# ProProject_Access_Control_KMX_Switch_202.net
KiCad netlist of a schematic drawn in EasyEDA Pro
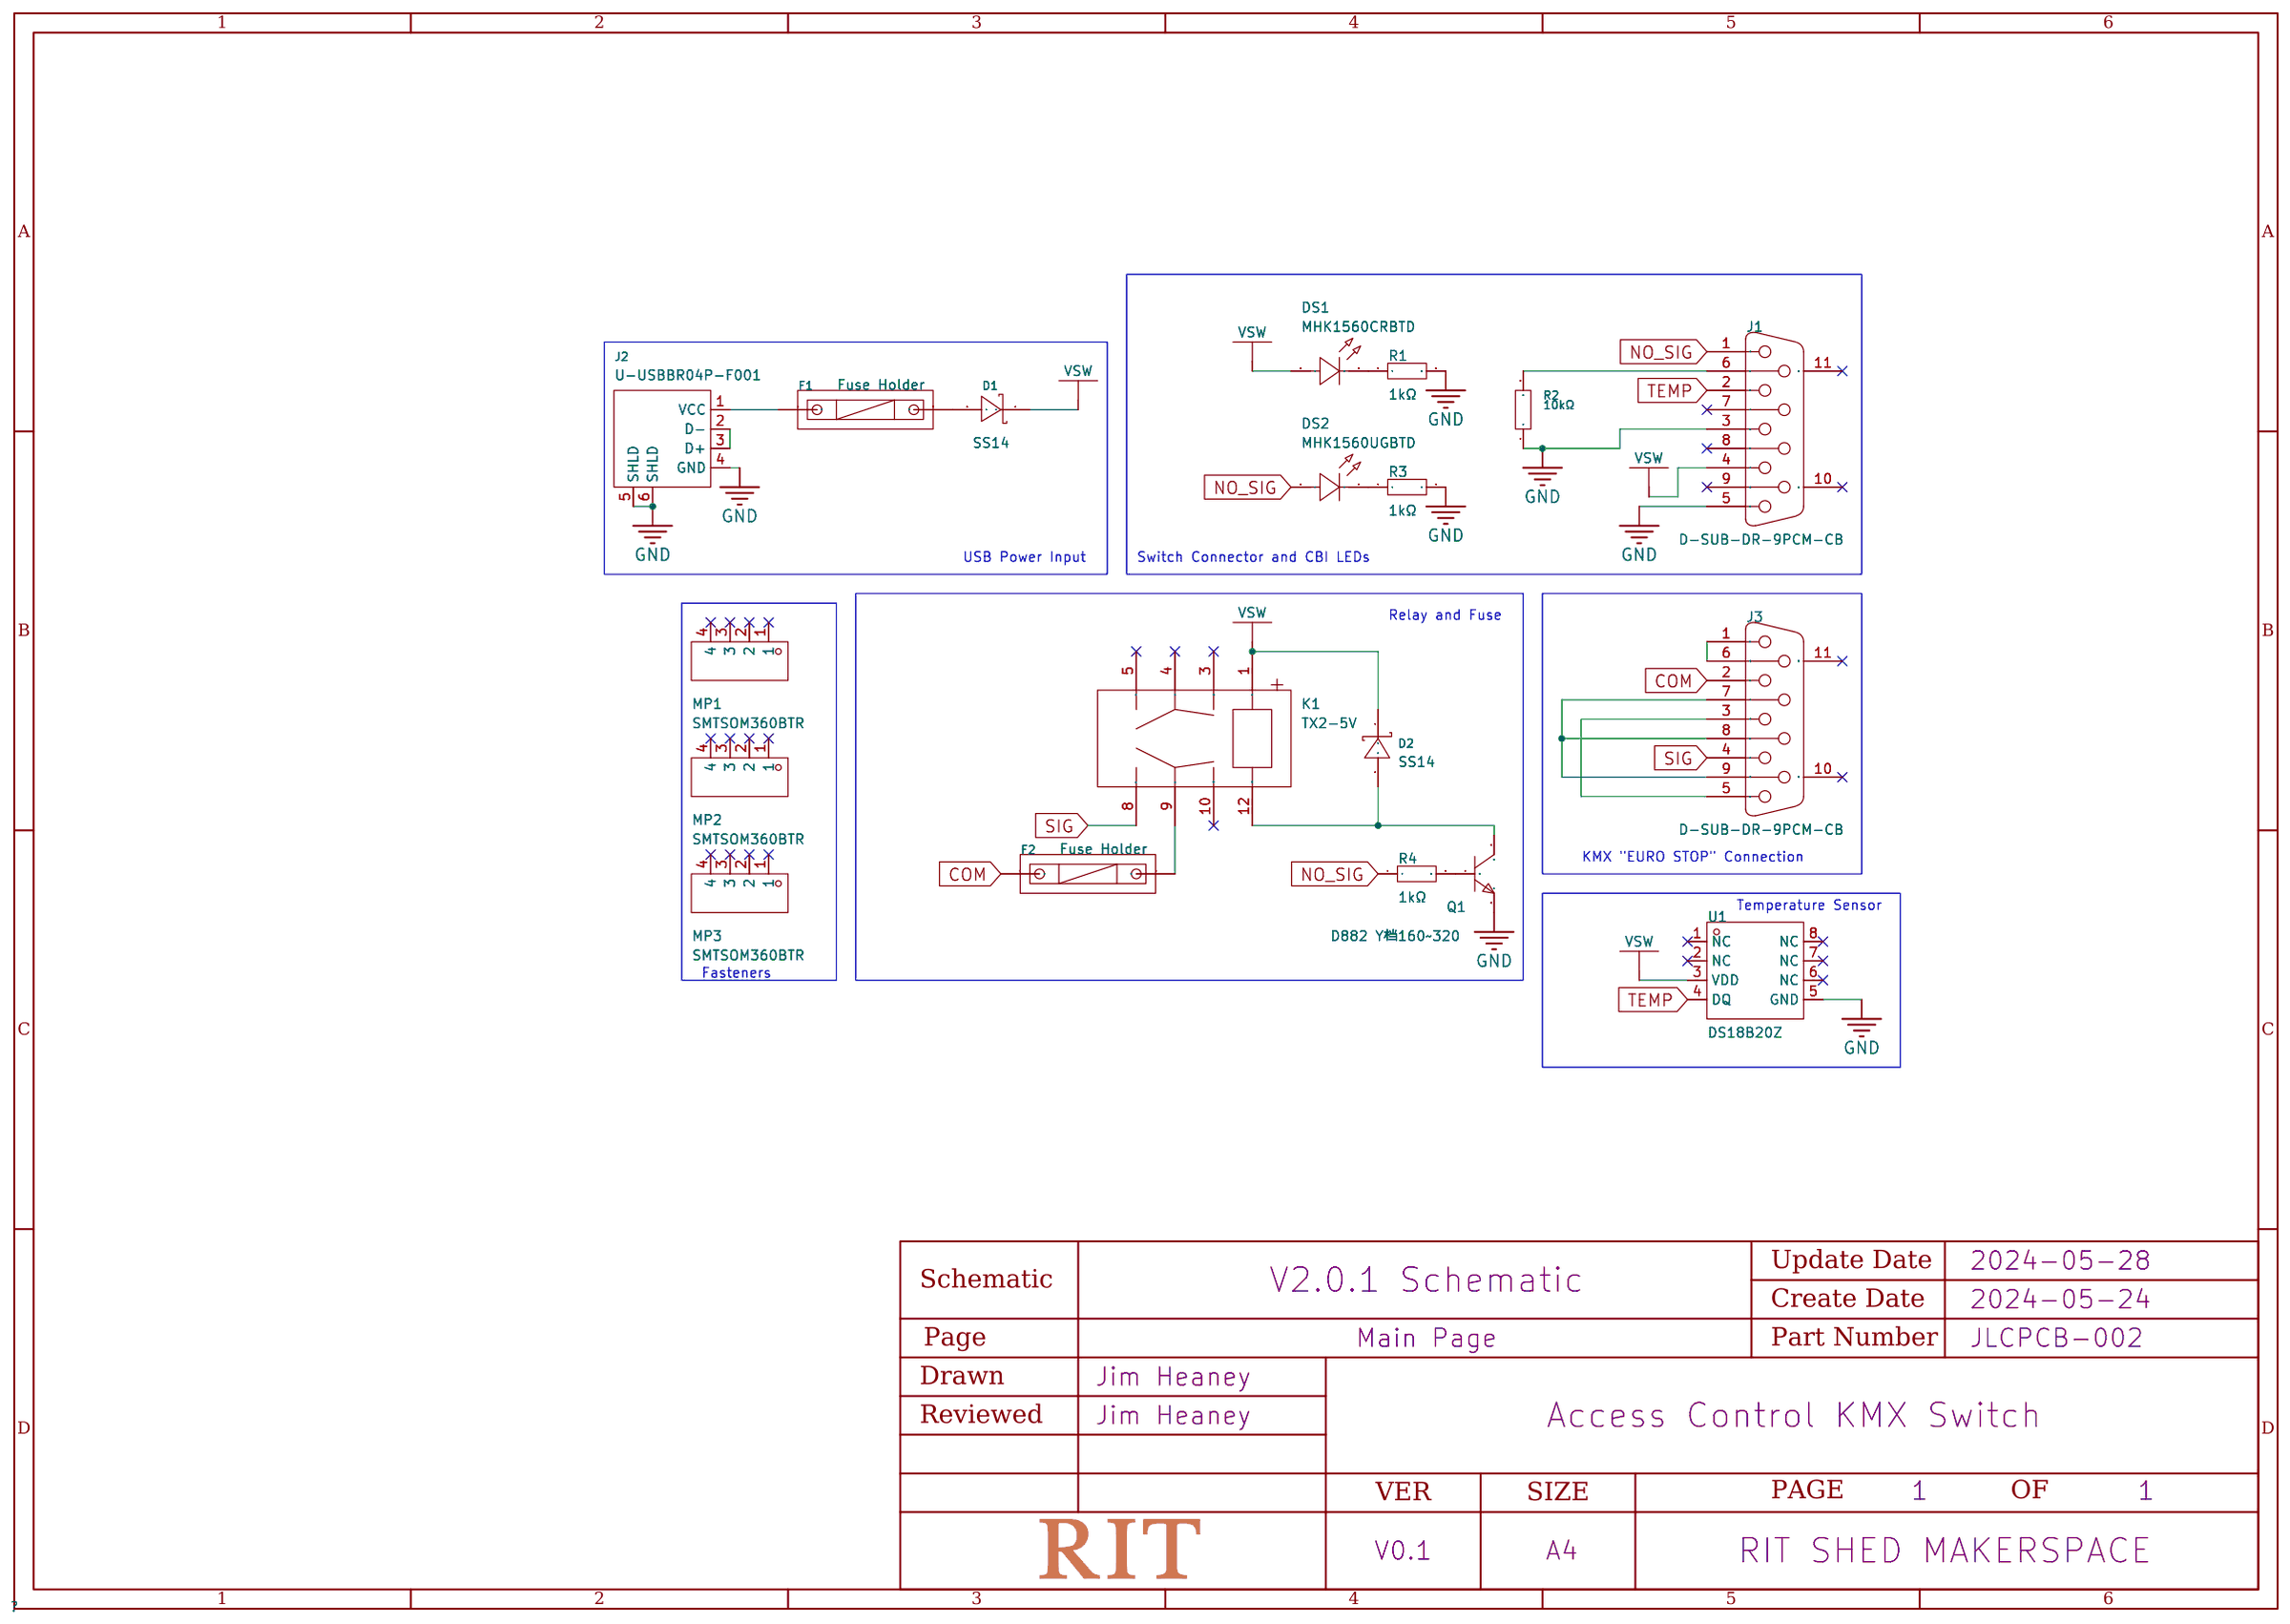
[diagram p0: schematic sheet]

(export (version "E")
  (design (tool "Eeschema 10.0.6"))
  (components
    (comp (ref "D1")
      (value "SS14")
      (footprint "easyedapro:SMA_L4.2-W2.6-LS5.3-RD")
      (fields (field (name "Manufacturer") "MDD"))
      (libsource (lib "easyedapro") (part "SS14"))
    )
    (comp (ref "D2")
      (value "SS14")
      (footprint "easyedapro:SMA_L4.2-W2.6-LS5.3-RD")
      (fields (field (name "Manufacturer") "MDD"))
      (libsource (lib "easyedapro") (part "SS14"))
    )
    (comp (ref "DS1")
      (value "MHK1560CRBTD")
      (footprint "easyedapro:LED-TH_MHK1560UGBTD")
      (fields (field (name "Manufacturer") "MEIHUA(美华)"))
      (libsource (lib "easyedapro") (part "MHK1560CGBTD"))
    )
    (comp (ref "DS2")
      (value "MHK1560UGBTD")
      (footprint "easyedapro:LED-TH_MHK1560UGBTD")
      (fields (field (name "Manufacturer") "MEIHUA(美华)"))
      (libsource (lib "easyedapro") (part "MHK1560UGBTD"))
    )
    (comp (ref "F1")
      (value "Fuse Holder")
      (footprint "easyedapro:FUSE-TH_L24.5-W9.8-P22.5")
      (description "Fuseholder Type:- Fuse Type:- Fuse Size:-")
      (fields (field (name "Manufacturer Part") "保险丝透明座") (field (name "Manufacturer") "xcfuse(旭程)"))
      (libsource (lib "easyedapro") (part "Fuse transparent seat"))
    )
    (comp (ref "F2")
      (value "Fuse Holder")
      (footprint "easyedapro:FUSE-TH_L24.5-W9.8-P22.5")
      (description "Fuseholder Type:- Fuse Type:- Fuse Size:-")
      (fields (field (name "Manufacturer Part") "保险丝透明座") (field (name "Manufacturer") "xcfuse(旭程)"))
      (libsource (lib "easyedapro") (part "Fuse transparent seat"))
    )
    (comp (ref "J1")
      (value "D-SUB-DR-9PCM-CB")
      (footprint "easyedapro:DB9-TH_ID09S33E4GV00LF")
      (fields (field (name "Manufacturer") "XUNPU(讯普)"))
      (libsource (lib "easyedapro") (part "D-SUB-DR-9PCM-CB"))
    )
    (comp (ref "J2")
      (value "U-USBBR04P-F001")
      (footprint "easyedapro:USB-B-TH_U241-041N-1BR85-1")
      (fields (field (name "Manufacturer") "Ckmtw(灿科盟)"))
      (libsource (lib "easyedapro") (part "U-USBBR04P-F001"))
    )
    (comp (ref "J3")
      (value "D-SUB-DR-9PCM-CB")
      (footprint "easyedapro:DB9-TH_ID09S33E4GV00LF")
      (fields (field (name "Manufacturer") "XUNPU(讯普)"))
      (libsource (lib "easyedapro") (part "D-SUB-DR-9PCM-CB"))
    )
    (comp (ref "K1")
      (value "TX2-5V")
      (footprint "easyedapro:RELAY-TH_TX2-3V")
      (fields (field (name "Manufacturer") "PANASONIC(松下)"))
      (libsource (lib "easyedapro") (part "TX2-5V"))
    )
    (comp (ref "MP1")
      (value "SMTSOM360BTR")
      (footprint "easyedapro:SMD_BD5.6-D4.1")
      (fields (field (name "Manufacturer") "YIYUAN(怡远)"))
      (libsource (lib "easyedapro") (part "SMTSOM360BTR"))
    )
    (comp (ref "MP2")
      (value "SMTSOM360BTR")
      (footprint "easyedapro:SMD_BD5.6-D4.1")
      (fields (field (name "Manufacturer") "YIYUAN(怡远)"))
      (libsource (lib "easyedapro") (part "SMTSOM360BTR"))
    )
    (comp (ref "MP3")
      (value "SMTSOM360BTR")
      (footprint "easyedapro:SMD_BD5.6-D4.1")
      (fields (field (name "Manufacturer") "YIYUAN(怡远)"))
      (libsource (lib "easyedapro") (part "SMTSOM360BTR"))
    )
    (comp (ref "Q1")
      (value "D882 Y档160~320")
      (footprint "easyedapro:SOT-89-3_L4.5-W2.5-P1.50-LS4.2-BR")
      (fields (field (name "Manufacturer") "CJ(江苏长电/长晶)"))
      (libsource (lib "easyedapro") (part "D882_C9634"))
    )
    (comp (ref "R1")
      (value "1kΩ")
      (footprint "easyedapro:R0805")
      (fields
        (field (name "Manufacturer Part") "0805W8F1001T5E")
        (field (name "Manufacturer") "UNI-ROYAL(厚声)")
      )
      (libsource (lib "easyedapro") (part "0805W8F1001T5E"))
    )
    (comp (ref "R2")
      (value "10kΩ")
      (footprint "easyedapro:R0805")
      (fields
        (field (name "Manufacturer Part") "0805W8F1002T5E")
        (field (name "Manufacturer") "UNI-ROYAL(厚声)")
      )
      (libsource (lib "easyedapro") (part "0805W8F1002T5E"))
    )
    (comp (ref "R3")
      (value "1kΩ")
      (footprint "easyedapro:R0805")
      (fields
        (field (name "Manufacturer Part") "0805W8F1001T5E")
        (field (name "Manufacturer") "UNI-ROYAL(厚声)")
      )
      (libsource (lib "easyedapro") (part "0805W8F1001T5E"))
    )
    (comp (ref "R4")
      (value "1kΩ")
      (footprint "easyedapro:R0805")
      (fields
        (field (name "Manufacturer Part") "0805W8F1001T5E")
        (field (name "Manufacturer") "UNI-ROYAL(厚声)")
      )
      (libsource (lib "easyedapro") (part "0805W8F1001T5E"))
    )
    (comp (ref "U1")
      (value "DS18B20Z")
      (footprint "easyedapro:SOP-8_L4.9-W3.9-P1.27-LS6.0-BL")
      (description "Resolution:±0.4°C Resolution:±0.4°C Supply Voltage:2.5V~5.5V Supply Voltage:2.5V~5.5V")
      (fields (field (name "Manufacturer") "UMW(友台半导体)"))
      (libsource (lib "easyedapro") (part "DS18B20Z"))
    )
  )
  (nets
    (net (code "1") (name "COM") (class "Default")
      (node (ref "F2") (pin "1") (pinfunction "1_1") (pintype "input"))
      (node (ref "J3") (pin "2") (pinfunction "2_2") (pintype "input"))
    )
    (net (code "2") (name "GND") (class "Default")
      (node (ref "J1") (pin "3") (pinfunction "3_3") (pintype "input"))
      (node (ref "J1") (pin "5") (pinfunction "5_5") (pintype "input"))
      (node (ref "J2") (pin "4") (pinfunction "GND_4") (pintype "input"))
      (node (ref "J2") (pin "5") (pinfunction "SHLD_5") (pintype "input"))
      (node (ref "J2") (pin "6") (pinfunction "SHLD_6") (pintype "input"))
      (node (ref "Q1") (pin "3") (pinfunction "E_3") (pintype "input"))
      (node (ref "R1") (pin "2") (pinfunction "2_2") (pintype "input"))
      (node (ref "R2") (pin "1") (pinfunction "1_1") (pintype "input"))
      (node (ref "R3") (pin "2") (pinfunction "2_2") (pintype "input"))
      (node (ref "U1") (pin "5") (pinfunction "GND_5") (pintype "unspecified"))
    )
    (net (code "3") (name "NO_SIG") (class "Default")
      (node (ref "DS2") (pin "2") (pinfunction "A_2") (pintype "unspecified"))
      (node (ref "J1") (pin "1") (pinfunction "1_1") (pintype "input"))
      (node (ref "R4") (pin "1") (pinfunction "1_1") (pintype "input"))
    )
    (net (code "4") (name "Net-(D1-A)") (class "Default")
      (node (ref "D1") (pin "2") (pinfunction "A_2") (pintype "input"))
      (node (ref "F1") (pin "2") (pinfunction "2_2") (pintype "input"))
    )
    (net (code "5") (name "Net-(D2-A)") (class "Default")
      (node (ref "D2") (pin "2") (pinfunction "A_2") (pintype "input"))
      (node (ref "K1") (pin "12") (pinfunction "12_12") (pintype "input"))
      (node (ref "Q1") (pin "2") (pinfunction "C_2") (pintype "input"))
    )
    (net (code "6") (name "Net-(DS1-K)") (class "Default")
      (node (ref "DS1") (pin "1") (pinfunction "K_1") (pintype "unspecified"))
      (node (ref "R1") (pin "1") (pinfunction "1_1") (pintype "input"))
    )
    (net (code "7") (name "Net-(DS2-K)") (class "Default")
      (node (ref "DS2") (pin "1") (pinfunction "K_1") (pintype "unspecified"))
      (node (ref "R3") (pin "1") (pinfunction "1_1") (pintype "input"))
    )
    (net (code "8") (name "Net-(F2-Pad2)") (class "Default")
      (node (ref "F2") (pin "2") (pinfunction "2_2") (pintype "input"))
      (node (ref "K1") (pin "9") (pinfunction "9_9") (pintype "input"))
    )
    (net (code "9") (name "Net-(J1-Pad6)") (class "Default")
      (node (ref "J1") (pin "6") (pinfunction "6_6") (pintype "input"))
      (node (ref "R2") (pin "2") (pinfunction "2_2") (pintype "input"))
    )
    (net (code "10") (name "Net-(J2-D+)") (class "Default")
      (node (ref "J2") (pin "2") (pinfunction "D-_2") (pintype "input"))
      (node (ref "J2") (pin "3") (pinfunction "D+_3") (pintype "input"))
    )
    (net (code "11") (name "Net-(J2-VCC)") (class "Default")
      (node (ref "F1") (pin "1") (pinfunction "1_1") (pintype "input"))
      (node (ref "J2") (pin "1") (pinfunction "VCC_1") (pintype "input"))
    )
    (net (code "12") (name "Net-(J3-Pad1)") (class "Default")
      (node (ref "J3") (pin "1") (pinfunction "1_1") (pintype "input"))
      (node (ref "J3") (pin "6") (pinfunction "6_6") (pintype "input"))
    )
    (net (code "13") (name "Net-(J3-Pad3)") (class "Default")
      (node (ref "J3") (pin "3") (pinfunction "3_3") (pintype "input"))
      (node (ref "J3") (pin "5") (pinfunction "5_5") (pintype "input"))
    )
    (net (code "14") (name "Net-(J3-Pad7)") (class "Default")
      (node (ref "J3") (pin "7") (pinfunction "7_7") (pintype "input"))
      (node (ref "J3") (pin "8") (pinfunction "8_8") (pintype "input"))
      (node (ref "J3") (pin "9") (pinfunction "9_9") (pintype "input"))
    )
    (net (code "15") (name "Net-(Q1-B)") (class "Default")
      (node (ref "Q1") (pin "1") (pinfunction "B_1") (pintype "input"))
      (node (ref "R4") (pin "2") (pinfunction "2_2") (pintype "input"))
    )
    (net (code "16") (name "SIG") (class "Default")
      (node (ref "J3") (pin "4") (pinfunction "4_4") (pintype "input"))
      (node (ref "K1") (pin "8") (pinfunction "8_8") (pintype "input"))
    )
    (net (code "17") (name "TEMP") (class "Default")
      (node (ref "J1") (pin "2") (pinfunction "2_2") (pintype "input"))
      (node (ref "U1") (pin "4") (pinfunction "DQ_4") (pintype "unspecified"))
    )
    (net (code "18") (name "VSW") (class "Default")
      (node (ref "D1") (pin "1") (pinfunction "K_1") (pintype "input"))
      (node (ref "D2") (pin "1") (pinfunction "K_1") (pintype "input"))
      (node (ref "DS1") (pin "2") (pinfunction "A_2") (pintype "unspecified"))
      (node (ref "J1") (pin "4") (pinfunction "4_4") (pintype "input"))
      (node (ref "K1") (pin "1") (pinfunction "1_1") (pintype "input"))
      (node (ref "U1") (pin "3") (pinfunction "VDD_3") (pintype "unspecified"))
    )
    (net (code "19") (name "unconnected-(J1-MH1-Pad10)") (class "Default")
      (node (ref "J1") (pin "10") (pinfunction "MH1_10") (pintype "input+no_connect"))
    )
    (net (code "20") (name "unconnected-(J1-MH2-Pad11)") (class "Default")
      (node (ref "J1") (pin "11") (pinfunction "MH2_11") (pintype "input+no_connect"))
    )
    (net (code "21") (name "unconnected-(J1-Pad7)") (class "Default")
      (node (ref "J1") (pin "7") (pinfunction "7_7") (pintype "input+no_connect"))
    )
    (net (code "22") (name "unconnected-(J1-Pad8)") (class "Default")
      (node (ref "J1") (pin "8") (pinfunction "8_8") (pintype "input+no_connect"))
    )
    (net (code "23") (name "unconnected-(J1-Pad9)") (class "Default")
      (node (ref "J1") (pin "9") (pinfunction "9_9") (pintype "input+no_connect"))
    )
    (net (code "24") (name "unconnected-(J3-MH1-Pad10)") (class "Default")
      (node (ref "J3") (pin "10") (pinfunction "MH1_10") (pintype "input+no_connect"))
    )
    (net (code "25") (name "unconnected-(J3-MH2-Pad11)") (class "Default")
      (node (ref "J3") (pin "11") (pinfunction "MH2_11") (pintype "input+no_connect"))
    )
    (net (code "26") (name "unconnected-(K1-Pad3)") (class "Default")
      (node (ref "K1") (pin "3") (pinfunction "3_3") (pintype "input+no_connect"))
    )
    (net (code "27") (name "unconnected-(K1-Pad4)") (class "Default")
      (node (ref "K1") (pin "4") (pinfunction "4_4") (pintype "input+no_connect"))
    )
    (net (code "28") (name "unconnected-(K1-Pad5)") (class "Default")
      (node (ref "K1") (pin "5") (pinfunction "5_5") (pintype "input+no_connect"))
    )
    (net (code "29") (name "unconnected-(K1-Pad10)") (class "Default")
      (node (ref "K1") (pin "10") (pinfunction "10_10") (pintype "input+no_connect"))
    )
    (net (code "30") (name "unconnected-(MP1-Pad1)") (class "Default")
      (node (ref "MP1") (pin "1") (pinfunction "1_1") (pintype "unspecified+no_connect"))
    )
    (net (code "31") (name "unconnected-(MP1-Pad2)") (class "Default")
      (node (ref "MP1") (pin "2") (pinfunction "2_2") (pintype "unspecified+no_connect"))
    )
    (net (code "32") (name "unconnected-(MP1-Pad3)") (class "Default")
      (node (ref "MP1") (pin "3") (pinfunction "3_3") (pintype "unspecified+no_connect"))
    )
    (net (code "33") (name "unconnected-(MP1-Pad4)") (class "Default")
      (node (ref "MP1") (pin "4") (pinfunction "4_4") (pintype "unspecified+no_connect"))
    )
    (net (code "34") (name "unconnected-(MP2-Pad1)") (class "Default")
      (node (ref "MP2") (pin "1") (pinfunction "1_1") (pintype "unspecified+no_connect"))
    )
    (net (code "35") (name "unconnected-(MP2-Pad2)") (class "Default")
      (node (ref "MP2") (pin "2") (pinfunction "2_2") (pintype "unspecified+no_connect"))
    )
    (net (code "36") (name "unconnected-(MP2-Pad3)") (class "Default")
      (node (ref "MP2") (pin "3") (pinfunction "3_3") (pintype "unspecified+no_connect"))
    )
    (net (code "37") (name "unconnected-(MP2-Pad4)") (class "Default")
      (node (ref "MP2") (pin "4") (pinfunction "4_4") (pintype "unspecified+no_connect"))
    )
    (net (code "38") (name "unconnected-(MP3-Pad1)") (class "Default")
      (node (ref "MP3") (pin "1") (pinfunction "1_1") (pintype "unspecified+no_connect"))
    )
    (net (code "39") (name "unconnected-(MP3-Pad2)") (class "Default")
      (node (ref "MP3") (pin "2") (pinfunction "2_2") (pintype "unspecified+no_connect"))
    )
    (net (code "40") (name "unconnected-(MP3-Pad3)") (class "Default")
      (node (ref "MP3") (pin "3") (pinfunction "3_3") (pintype "unspecified+no_connect"))
    )
    (net (code "41") (name "unconnected-(MP3-Pad4)") (class "Default")
      (node (ref "MP3") (pin "4") (pinfunction "4_4") (pintype "unspecified+no_connect"))
    )
    (net (code "42") (name "unconnected-(U1-NC-Pad1)") (class "Default")
      (node (ref "U1") (pin "1") (pinfunction "NC_1") (pintype "unspecified+no_connect"))
    )
    (net (code "43") (name "unconnected-(U1-NC-Pad2)") (class "Default")
      (node (ref "U1") (pin "2") (pinfunction "NC_2") (pintype "unspecified+no_connect"))
    )
    (net (code "44") (name "unconnected-(U1-NC-Pad6)") (class "Default")
      (node (ref "U1") (pin "6") (pinfunction "NC_6") (pintype "unspecified+no_connect"))
    )
    (net (code "45") (name "unconnected-(U1-NC-Pad7)") (class "Default")
      (node (ref "U1") (pin "7") (pinfunction "NC_7") (pintype "unspecified+no_connect"))
    )
    (net (code "46") (name "unconnected-(U1-NC-Pad8)") (class "Default")
      (node (ref "U1") (pin "8") (pinfunction "NC_8") (pintype "unspecified+no_connect"))
    )
  )
)
